# USB_Current_Sensor.net
KiCad netlist of a schematic drawn in EAGLE
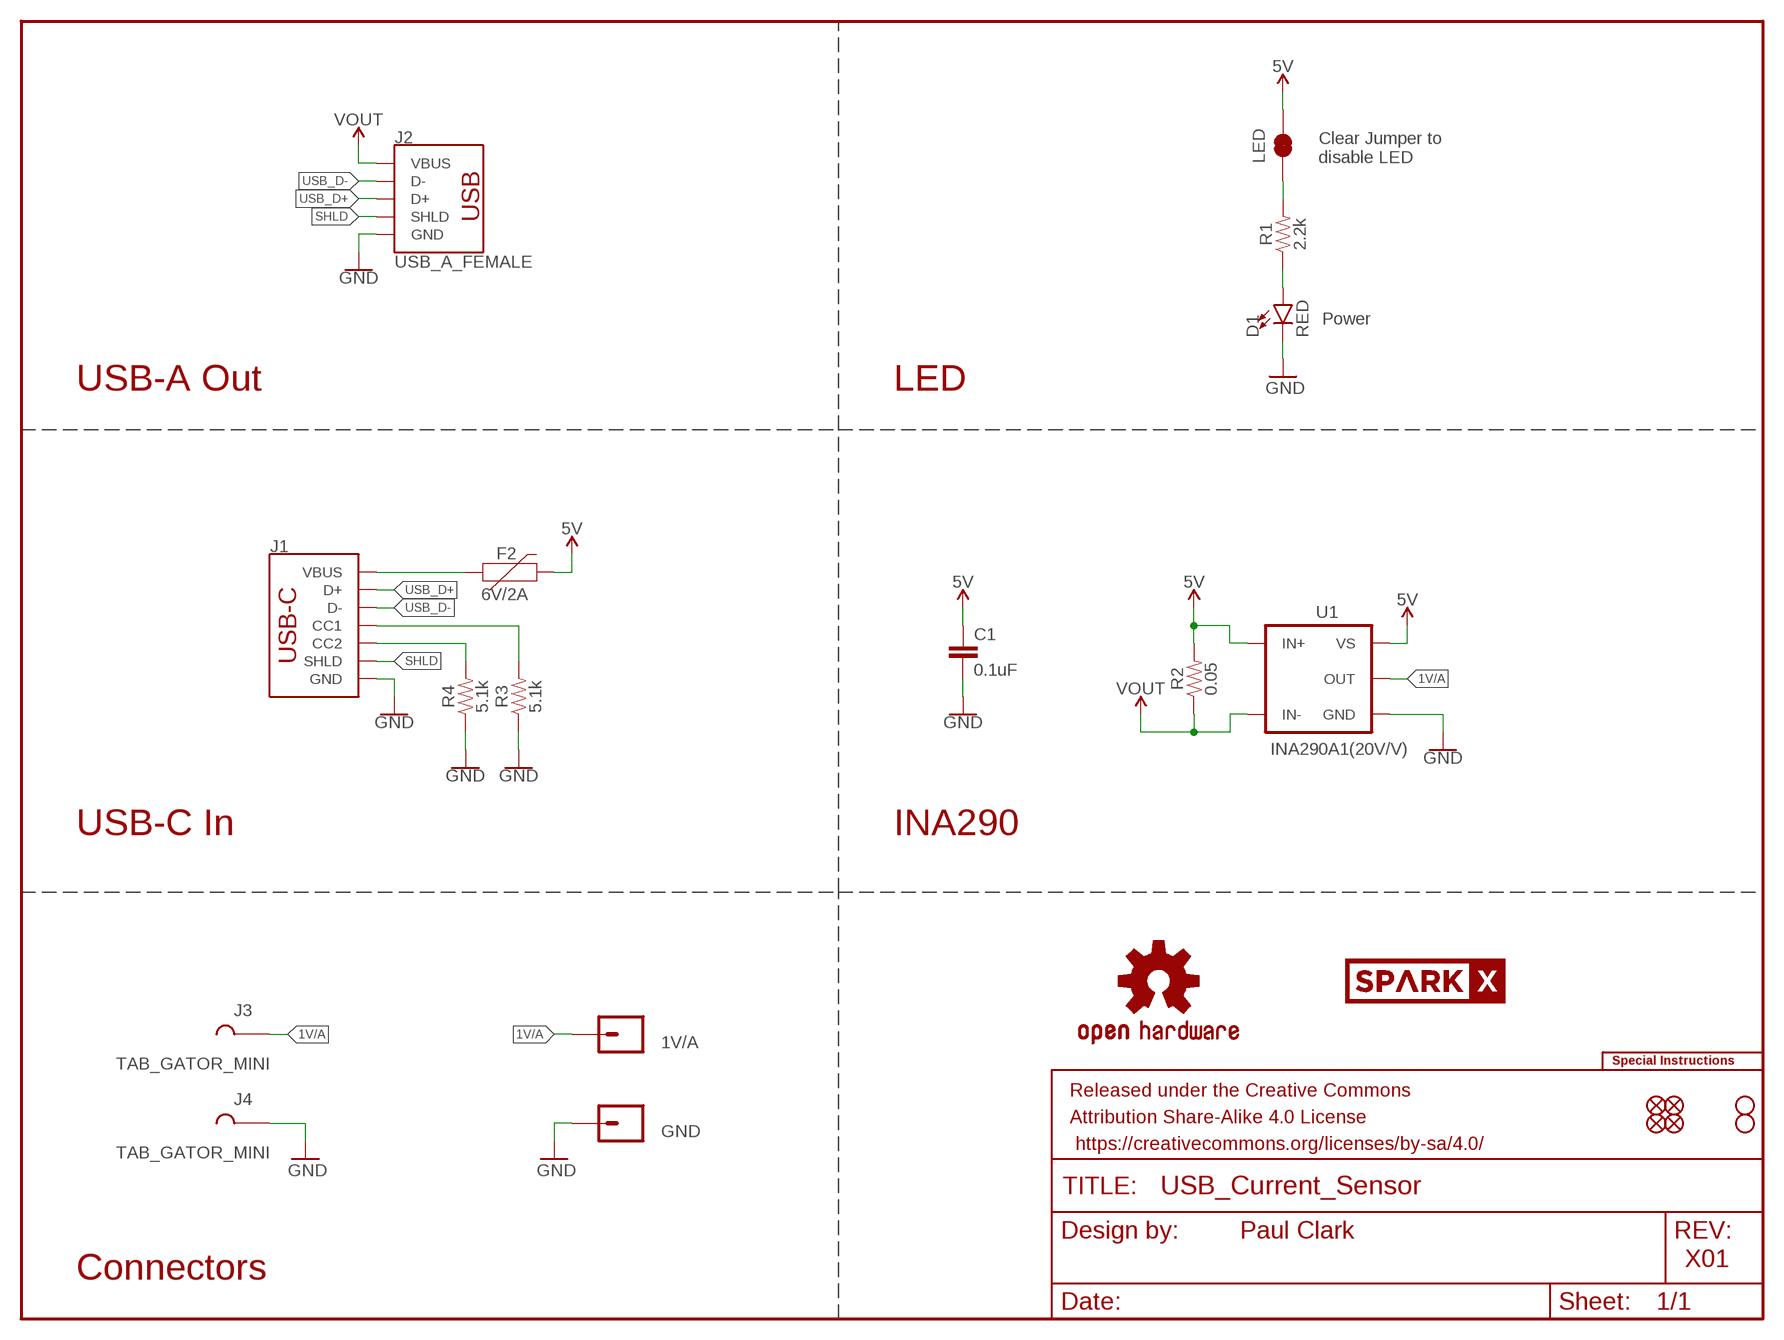
[diagram p0: schematic, sheet 1]

(export (version "E")
  (design (tool "Eeschema 10.0.6"))
  (components
    (comp (ref "1V/A")
      (value "CONN_01PTH_NO_SILK_YES_STOP")
      (footprint "eagle-import:1X01_NO_SILK")
      (libsource (lib "eagle-import") (part "CONN_01PTH_NO_SILK_YES_STOP"))
    )
    (comp (ref "C1")
      (value "0.1uF")
      (footprint "eagle-import:0603")
      (libsource (lib "eagle-import") (part "0.1UF-0603-25V-(+80/-20%)"))
    )
    (comp (ref "D1")
      (value "RED")
      (footprint "eagle-import:LED-0603")
      (libsource (lib "eagle-import") (part "LED-RED0603"))
    )
    (comp (ref "F2")
      (value "6V/2A")
      (footprint "eagle-import:1210")
      (libsource (lib "eagle-import") (part "PPTC_6V2A"))
    )
    (comp (ref "FRAME1")
      (value "FRAME-LETTER")
      (footprint "eagle-import:CREATIVE_COMMONS")
      (libsource (lib "eagle-import") (part "FRAME-LETTER"))
    )
    (comp (ref "GND")
      (value "CONN_01PTH_NO_SILK_YES_STOP")
      (footprint "eagle-import:1X01_NO_SILK")
      (libsource (lib "eagle-import") (part "CONN_01PTH_NO_SILK_YES_STOP"))
    )
    (comp (ref "J1")
      (value "USB_C_4-LAYER_PADS")
      (footprint "eagle-import:USB-C-16P_4LAYER-PADS")
      (libsource (lib "eagle-import") (part "USB_C_4-LAYER_PADS"))
    )
    (comp (ref "J2")
      (value "USB_A_FEMALE")
      (footprint "eagle-import:USB-A-S-NOSILK-FEMALE")
      (libsource (lib "eagle-import") (part "USB_A_SMT_FEMALE_NS"))
    )
    (comp (ref "J3")
      (value "TAB_GATOR_MINI")
      (footprint "eagle-import:TAB_GATOR_MINI")
      (libsource (lib "eagle-import") (part "TAB_GATOR_MINI"))
    )
    (comp (ref "J4")
      (value "TAB_GATOR_MINI")
      (footprint "eagle-import:TAB_GATOR_MINI")
      (libsource (lib "eagle-import") (part "TAB_GATOR_MINI"))
    )
    (comp (ref "JP1")
      (value "FIDUCIAL1X2")
      (footprint "eagle-import:FIDUCIAL-1X2")
      (libsource (lib "eagle-import") (part "FIDUCIAL1X2"))
    )
    (comp (ref "JP2")
      (value "FIDUCIAL1X2")
      (footprint "eagle-import:FIDUCIAL-1X2")
      (libsource (lib "eagle-import") (part "FIDUCIAL1X2"))
    )
    (comp (ref "JP3")
      (value "STAND-OFF")
      (footprint "eagle-import:STAND-OFF")
      (libsource (lib "eagle-import") (part "STAND-OFF"))
    )
    (comp (ref "JP4")
      (value "STAND-OFF")
      (footprint "eagle-import:STAND-OFF")
      (libsource (lib "eagle-import") (part "STAND-OFF"))
    )
    (comp (ref "JP5")
      (value "FIDUCIAL1X2")
      (footprint "eagle-import:FIDUCIAL-1X2")
      (libsource (lib "eagle-import") (part "FIDUCIAL1X2"))
    )
    (comp (ref "JP6")
      (value "FIDUCIAL1X2")
      (footprint "eagle-import:FIDUCIAL-1X2")
      (libsource (lib "eagle-import") (part "FIDUCIAL1X2"))
    )
    (comp (ref "LED")
      (value "JUMPER-SMT_2_NC_TRACE_SILK")
      (footprint "eagle-import:SMT-JUMPER_2_NC_TRACE_SILK")
      (libsource (lib "eagle-import") (part "JUMPER-SMT_2_NC_TRACE_SILK"))
    )
    (comp (ref "LOGO1")
      (value "OSHW-LOGOMINI")
      (footprint "eagle-import:OSHW-LOGO-MINI")
      (libsource (lib "eagle-import") (part "OSHW-LOGOMINI"))
    )
    (comp (ref "LOGO2")
      (value "SPECIAL_INSTRUCTIONS-ORDERING")
      (footprint "eagle-import:ORDERING_INSTRUCTIONS")
      (libsource (lib "eagle-import") (part "SPECIAL_INSTRUCTIONS-ORDERING"))
    )
    (comp (ref "R1")
      (value "2.2k")
      (footprint "eagle-import:0603")
      (libsource (lib "eagle-import") (part "2.2KOHM-0603-1/10W-1%"))
    )
    (comp (ref "R2")
      (value "0.05")
      (footprint "eagle-import:0603")
      (libsource (lib "eagle-import") (part "0.05OHM-0603-1/5W-1%"))
    )
    (comp (ref "R3")
      (value "5.1k")
      (footprint "eagle-import:0603")
      (libsource (lib "eagle-import") (part "5.1KOHM5.1KOHM-0603-1/10W-1%"))
    )
    (comp (ref "R4")
      (value "5.1k")
      (footprint "eagle-import:0603")
      (libsource (lib "eagle-import") (part "5.1KOHM5.1KOHM-0603-1/10W-1%"))
    )
    (comp (ref "U$2")
      (value "SPARKX-LOGO4")
      (footprint "eagle-import:SPARKX-MEDIUM")
      (libsource (lib "eagle-import") (part "SPARKX-LOGO4"))
    )
    (comp (ref "U1")
      (value "INA290A1(20V/V)")
      (footprint "eagle-import:SC70")
      (libsource (lib "eagle-import") (part "INA290A1(20V/V)"))
    )
  )
  (nets
    (net (code "1") (name "1V{slash}A") (class "Default")
      (node (ref "1V/A") (pin "1") (pinfunction "1_1") (pintype "passive"))
      (node (ref "J3") (pin "P1") (pinfunction "P$1_P1") (pintype "bidirectional"))
      (node (ref "U1") (pin "1") (pinfunction "OUT_1") (pintype "output"))
    )
    (net (code "2") (name "5V") (class "Default")
      (node (ref "C1") (pin "1") (pinfunction "1_1") (pintype "passive"))
      (node (ref "F2") (pin "2") (pinfunction "2_2") (pintype "bidirectional"))
      (node (ref "LED") (pin "2") (pinfunction "2_2") (pintype "passive"))
      (node (ref "R2") (pin "2") (pinfunction "2_2") (pintype "passive"))
      (node (ref "U1") (pin "3") (pinfunction "VS_3") (pintype "power_in"))
      (node (ref "U1") (pin "4") (pinfunction "IN+_4") (pintype "input"))
    )
    (net (code "3") (name "GND") (class "Default")
      (node (ref "C1") (pin "2") (pinfunction "2_2") (pintype "passive"))
      (node (ref "D1") (pin "C") (pinfunction "C_C") (pintype "passive"))
      (node (ref "GND") (pin "1") (pinfunction "1_1") (pintype "passive"))
      (node (ref "J1") (pin "GND") (pinfunction "GND_GND") (pintype "bidirectional"))
      (node (ref "J1") (pin "GND2") (pinfunction "GND_GND2") (pintype "bidirectional"))
      (node (ref "J2") (pin "GND") (pinfunction "GND_GND") (pintype "power_in"))
      (node (ref "J4") (pin "P1") (pinfunction "P$1_P1") (pintype "bidirectional"))
      (node (ref "R3") (pin "1") (pinfunction "1_1") (pintype "passive"))
      (node (ref "R4") (pin "1") (pinfunction "1_1") (pintype "passive"))
      (node (ref "U1") (pin "2") (pinfunction "GND_2") (pintype "power_in"))
    )
    (net (code "4") (name "Net-(D1-PadA)") (class "Default")
      (node (ref "D1") (pin "A") (pinfunction "A_A") (pintype "passive"))
      (node (ref "R1") (pin "1") (pinfunction "1_1") (pintype "passive"))
    )
    (net (code "5") (name "Net-(F2-Pad1)") (class "Default")
      (node (ref "F2") (pin "1") (pinfunction "1_1") (pintype "bidirectional"))
      (node (ref "J1") (pin "VBUS1") (pinfunction "VBUS_VBUS1") (pintype "bidirectional"))
      (node (ref "J1") (pin "VBUS2") (pinfunction "VBUS_VBUS2") (pintype "bidirectional"))
    )
    (net (code "6") (name "Net-(J1-CC1)") (class "Default")
      (node (ref "J1") (pin "A5") (pinfunction "CC1_A5") (pintype "bidirectional"))
      (node (ref "R3") (pin "2") (pinfunction "2_2") (pintype "passive"))
    )
    (net (code "7") (name "Net-(J1-CC2)") (class "Default")
      (node (ref "J1") (pin "B5") (pinfunction "CC2_B5") (pintype "bidirectional"))
      (node (ref "R4") (pin "2") (pinfunction "2_2") (pintype "passive"))
    )
    (net (code "8") (name "Net-(LED-Pad1)") (class "Default")
      (node (ref "LED") (pin "1") (pinfunction "1_1") (pintype "passive"))
      (node (ref "R1") (pin "2") (pinfunction "2_2") (pintype "passive"))
    )
    (net (code "9") (name "SHLD") (class "Default")
      (node (ref "J1") (pin "SHLD1") (pinfunction "SHLD_SHLD1") (pintype "bidirectional"))
      (node (ref "J1") (pin "SHLD2") (pinfunction "SHLD_SHLD2") (pintype "bidirectional"))
      (node (ref "J1") (pin "SHLD3") (pinfunction "SHLD_SHLD3") (pintype "bidirectional"))
      (node (ref "J1") (pin "SHLD4") (pinfunction "SHLD_SHLD4") (pintype "bidirectional"))
      (node (ref "J2") (pin "SHLD1") (pinfunction "SHLD_SHLD1") (pintype "bidirectional"))
      (node (ref "J2") (pin "SHLD2") (pinfunction "SHLD_SHLD2") (pintype "bidirectional"))
    )
    (net (code "10") (name "USB_D+") (class "Default")
      (node (ref "J1") (pin "A6") (pinfunction "D+_A6") (pintype "bidirectional"))
      (node (ref "J1") (pin "B6") (pinfunction "D+_B6") (pintype "bidirectional"))
      (node (ref "J2") (pin "D+") (pinfunction "D+_D+") (pintype "bidirectional"))
    )
    (net (code "11") (name "USB_D-") (class "Default")
      (node (ref "J1") (pin "A7") (pinfunction "D-_A7") (pintype "bidirectional"))
      (node (ref "J1") (pin "B7") (pinfunction "D-_B7") (pintype "bidirectional"))
      (node (ref "J2") (pin "D-") (pinfunction "D-_D-") (pintype "bidirectional"))
    )
    (net (code "12") (name "VOUT") (class "Default")
      (node (ref "J2") (pin "VBUS") (pinfunction "VBUS_VBUS") (pintype "power_in"))
      (node (ref "R2") (pin "1") (pinfunction "1_1") (pintype "passive"))
      (node (ref "U1") (pin "5") (pinfunction "IN-_5") (pintype "input"))
    )
  )
)
